# pylontec_LAN_interface.net
KiCad netlist of a schematic drawn in EAGLE
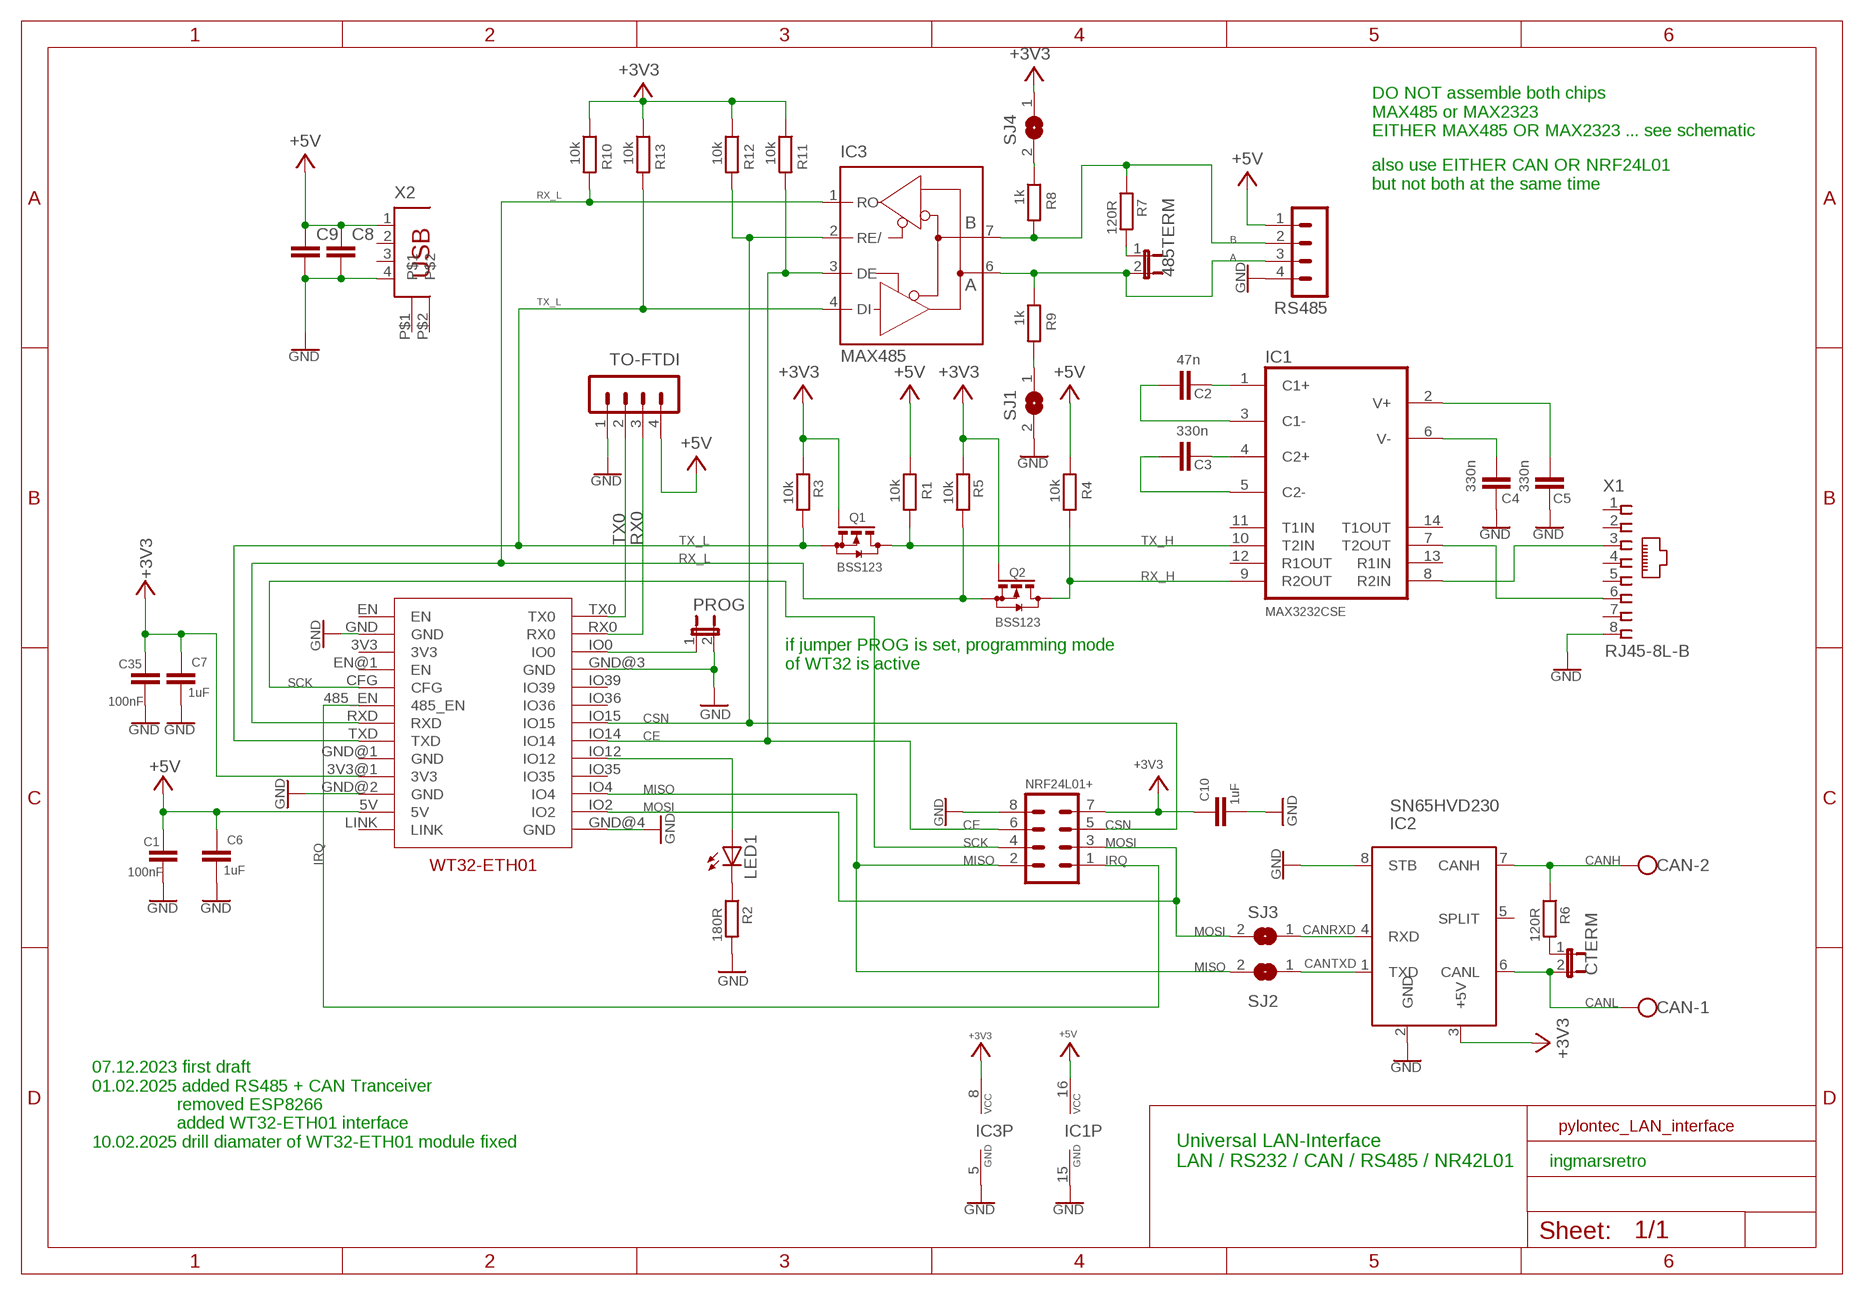
[diagram p0: schematic, sheet 1]

(export (version "E")
  (design (tool "Eeschema 10.0.6"))
  (components
    (comp (ref "485TERM")
      (value "JP1E")
      (footprint "eagle-import:JP1")
      (libsource (lib "eagle-import") (part "JP1E"))
    )
    (comp (ref "C1")
      (value "100nF")
      (footprint "eagle-import:C0805")
      (libsource (lib "eagle-import") (part "resistor_C-EUC0805"))
    )
    (comp (ref "C2")
      (value "47n")
      (footprint "eagle-import:C0805")
      (libsource (lib "eagle-import") (part "resistor_C-EUC0805"))
    )
    (comp (ref "C3")
      (value "330n")
      (footprint "eagle-import:C0805")
      (libsource (lib "eagle-import") (part "resistor_C-EUC0805"))
    )
    (comp (ref "C4")
      (value "330n")
      (footprint "eagle-import:C0805")
      (libsource (lib "eagle-import") (part "resistor_C-EUC0805"))
    )
    (comp (ref "C5")
      (value "330n")
      (footprint "eagle-import:C0805")
      (libsource (lib "eagle-import") (part "resistor_C-EUC0805"))
    )
    (comp (ref "C6")
      (value "1uF")
      (footprint "eagle-import:C1210")
      (libsource (lib "eagle-import") (part "C-EUC1210"))
    )
    (comp (ref "C7")
      (value "1uF")
      (footprint "eagle-import:C1210")
      (libsource (lib "eagle-import") (part "C-EUC1210"))
    )
    (comp (ref "C8")
      (value "C-EUC1210")
      (footprint "eagle-import:C1210")
      (libsource (lib "eagle-import") (part "C-EUC1210"))
    )
    (comp (ref "C9")
      (value "C-EUC1210")
      (footprint "eagle-import:C1210")
      (libsource (lib "eagle-import") (part "C-EUC1210"))
    )
    (comp (ref "C10")
      (value "1uF")
      (footprint "eagle-import:C1210")
      (libsource (lib "eagle-import") (part "C-EUC1210"))
    )
    (comp (ref "C35")
      (value "100nF")
      (footprint "eagle-import:C0805")
      (libsource (lib "eagle-import") (part "resistor_C-EUC0805"))
    )
    (comp (ref "CAN")
      (value "W237-102")
      (footprint "eagle-import:W237-102")
      (fields (field (name "MPN") "237-102"))
      (libsource (lib "eagle-import") (part "W237-102"))
    )
    (comp (ref "CTERM")
      (value "JP1E")
      (footprint "eagle-import:JP1")
      (libsource (lib "eagle-import") (part "JP1E"))
    )
    (comp (ref "IC1")
      (value "MAX3232CSE")
      (footprint "eagle-import:SO16")
      (libsource (lib "eagle-import") (part "MAX3232SEC"))
    )
    (comp (ref "IC2")
      (value "SN65HVD230")
      (footprint "eagle-import:SO8")
      (libsource (lib "eagle-import") (part "TJA1040"))
    )
    (comp (ref "IC3")
      (value "MAX485")
      (footprint "eagle-import:SO08")
      (fields (field (name "MF") "MAXIM") (field (name "MPN") "MAX481CSA"))
      (libsource (lib "eagle-import") (part "MAX481CSA"))
    )
    (comp (ref "LED1")
      (value "LED_LEDCHIPLED_0805")
      (footprint "eagle-import:LED_CHIPLED_0805")
      (libsource (lib "eagle-import") (part "LED_LEDCHIPLED_0805"))
    )
    (comp (ref "NRF24L01+")
      (value "MA04-2")
      (footprint "eagle-import:MA04-2")
      (libsource (lib "eagle-import") (part "MA04-2"))
    )
    (comp (ref "PROG")
      (value "JP1E")
      (footprint "eagle-import:JP1")
      (libsource (lib "eagle-import") (part "JP1E"))
    )
    (comp (ref "Q1")
      (value "BSS123")
      (footprint "eagle-import:SOT23")
      (libsource (lib "eagle-import") (part "BSS123"))
    )
    (comp (ref "Q2")
      (value "BSS123")
      (footprint "eagle-import:SOT23")
      (libsource (lib "eagle-import") (part "BSS123"))
    )
    (comp (ref "R1")
      (value "10k")
      (footprint "eagle-import:R0805")
      (libsource (lib "eagle-import") (part "R-EU_R0805"))
    )
    (comp (ref "R2")
      (value "180R")
      (footprint "eagle-import:R0805")
      (libsource (lib "eagle-import") (part "R-EU_R0805"))
    )
    (comp (ref "R3")
      (value "10k")
      (footprint "eagle-import:R0805")
      (libsource (lib "eagle-import") (part "R-EU_R0805"))
    )
    (comp (ref "R4")
      (value "10k")
      (footprint "eagle-import:R0805")
      (libsource (lib "eagle-import") (part "R-EU_R0805"))
    )
    (comp (ref "R5")
      (value "10k")
      (footprint "eagle-import:R0805")
      (libsource (lib "eagle-import") (part "R-EU_R0805"))
    )
    (comp (ref "R6")
      (value "120R")
      (footprint "eagle-import:R0805")
      (libsource (lib "eagle-import") (part "R-EU_R0805"))
    )
    (comp (ref "R7")
      (value "120R")
      (footprint "eagle-import:R0805")
      (libsource (lib "eagle-import") (part "R-EU_R0805"))
    )
    (comp (ref "R8")
      (value "1k")
      (footprint "eagle-import:R0805")
      (libsource (lib "eagle-import") (part "R-EU_R0805"))
    )
    (comp (ref "R9")
      (value "1k")
      (footprint "eagle-import:R0805")
      (libsource (lib "eagle-import") (part "R-EU_R0805"))
    )
    (comp (ref "R10")
      (value "10k")
      (footprint "eagle-import:R0805")
      (libsource (lib "eagle-import") (part "R-EU_R0805"))
    )
    (comp (ref "R11")
      (value "10k")
      (footprint "eagle-import:R0805")
      (libsource (lib "eagle-import") (part "R-EU_R0805"))
    )
    (comp (ref "R12")
      (value "10k")
      (footprint "eagle-import:R0805")
      (libsource (lib "eagle-import") (part "R-EU_R0805"))
    )
    (comp (ref "R13")
      (value "10k")
      (footprint "eagle-import:R0805")
      (libsource (lib "eagle-import") (part "R-EU_R0805"))
    )
    (comp (ref "RS485")
      (value "MA04-1")
      (footprint "eagle-import:MA04-1")
      (libsource (lib "eagle-import") (part "MA04-1"))
    )
    (comp (ref "SJ1") (value "SJ") (footprint "eagle-import:SJ") (libsource (lib "eagle-import") (part "SJ")))
    (comp (ref "SJ2") (value "SJ") (footprint "eagle-import:SJ") (libsource (lib "eagle-import") (part "SJ")))
    (comp (ref "SJ3") (value "SJ") (footprint "eagle-import:SJ") (libsource (lib "eagle-import") (part "SJ")))
    (comp (ref "SJ4") (value "SJ") (footprint "eagle-import:SJ") (libsource (lib "eagle-import") (part "SJ")))
    (comp (ref "TO-FTDI")
      (value "MA04-1")
      (footprint "eagle-import:MA04-1")
      (libsource (lib "eagle-import") (part "MA04-1"))
    )
    (comp (ref "U$2")
      (value "WT32-ETH01")
      (footprint "eagle-import:WT32-ETH01")
      (fields (field (name "MF") "wireless-tag"))
      (libsource (lib "eagle-import") (part "WT32-ETH01"))
    )
    (comp (ref "X1")
      (value "RJ45-8L-B")
      (footprint "eagle-import:RJ45-NO-SHIELD")
      (fields (field (name "MF") "TYCO ELECTRONICS"))
      (libsource (lib "eagle-import") (part "RJ45-8L-B"))
    )
    (comp (ref "X2")
      (value "SMARTPRJ_PN61729")
      (footprint "eagle-import:SMARTPRJ_PN61729")
      (libsource (lib "eagle-import") (part "SMARTPRJ_PN61729"))
    )
  )
  (nets
    (net (code "1") (name "+3V3") (class "Default")
      (node (ref "C10") (pin "1") (pinfunction "1_1") (pintype "passive"))
      (node (ref "C35") (pin "2") (pinfunction "2_2") (pintype "passive"))
      (node (ref "C7") (pin "1") (pinfunction "1_1") (pintype "passive"))
      (node (ref "IC2") (pin "3") (pinfunction "+5V_3") (pintype "bidirectional"))
      (node (ref "IC3") (pin "8") (pinfunction "VCC_8") (pintype "power_in"))
      (node (ref "NRF24L01+") (pin "7") (pinfunction "7_7") (pintype "passive"))
      (node (ref "Q1") (pin "1") (pinfunction "G_1") (pintype "passive"))
      (node (ref "Q2") (pin "1") (pinfunction "G_1") (pintype "passive"))
      (node (ref "R10") (pin "1") (pinfunction "1_1") (pintype "passive"))
      (node (ref "R11") (pin "1") (pinfunction "1_1") (pintype "passive"))
      (node (ref "R12") (pin "1") (pinfunction "1_1") (pintype "passive"))
      (node (ref "R13") (pin "1") (pinfunction "1_1") (pintype "passive"))
      (node (ref "R3") (pin "1") (pinfunction "1_1") (pintype "passive"))
      (node (ref "R5") (pin "1") (pinfunction "1_1") (pintype "passive"))
      (node (ref "SJ4") (pin "1") (pinfunction "1_1") (pintype "passive"))
      (node (ref "U$2") (pin "3V3@1") (pinfunction "3V3_3V3@1") (pintype "bidirectional"))
    )
    (net (code "2") (name "+5V") (class "Default")
      (node (ref "C1") (pin "2") (pinfunction "2_2") (pintype "passive"))
      (node (ref "C6") (pin "1") (pinfunction "1_1") (pintype "passive"))
      (node (ref "C8") (pin "1") (pinfunction "1_1") (pintype "passive"))
      (node (ref "C9") (pin "1") (pinfunction "1_1") (pintype "passive"))
      (node (ref "IC1") (pin "16") (pinfunction "VCC_16") (pintype "power_in"))
      (node (ref "R1") (pin "1") (pinfunction "1_1") (pintype "passive"))
      (node (ref "R4") (pin "1") (pinfunction "1_1") (pintype "passive"))
      (node (ref "RS485") (pin "1") (pinfunction "1_1") (pintype "passive"))
      (node (ref "TO-FTDI") (pin "4") (pinfunction "4_4") (pintype "passive"))
      (node (ref "U$2") (pin "5V") (pinfunction "5V_5V") (pintype "bidirectional"))
      (node (ref "X2") (pin "1") (pinfunction "1_1") (pintype "bidirectional"))
    )
    (net (code "3") (name "/A") (class "Default")
      (node (ref "485TERM") (pin "2") (pinfunction "2_2") (pintype "passive"))
      (node (ref "IC3") (pin "6") (pinfunction "A_6") (pintype "passive"))
      (node (ref "R9") (pin "1") (pinfunction "1_1") (pintype "passive"))
      (node (ref "RS485") (pin "3") (pinfunction "3_3") (pintype "passive"))
    )
    (net (code "4") (name "/B") (class "Default")
      (node (ref "IC3") (pin "7") (pinfunction "B_7") (pintype "passive"))
      (node (ref "R7") (pin "1") (pinfunction "1_1") (pintype "passive"))
      (node (ref "R8") (pin "2") (pinfunction "2_2") (pintype "passive"))
      (node (ref "RS485") (pin "2") (pinfunction "2_2") (pintype "passive"))
    )
    (net (code "5") (name "/CANH") (class "Default")
      (node (ref "CAN") (pin "2") (pinfunction "KL_2") (pintype "passive"))
      (node (ref "IC2") (pin "7") (pinfunction "CANH_7") (pintype "bidirectional"))
      (node (ref "R6") (pin "1") (pinfunction "1_1") (pintype "passive"))
    )
    (net (code "6") (name "/CANL") (class "Default")
      (node (ref "CAN") (pin "1") (pinfunction "KL_1") (pintype "passive"))
      (node (ref "CTERM") (pin "2") (pinfunction "2_2") (pintype "passive"))
      (node (ref "IC2") (pin "6") (pinfunction "CANL_6") (pintype "bidirectional"))
    )
    (net (code "7") (name "/CANRXD") (class "Default")
      (node (ref "IC2") (pin "4") (pinfunction "RXD_4") (pintype "bidirectional"))
      (node (ref "SJ3") (pin "1") (pinfunction "1_1") (pintype "passive"))
    )
    (net (code "8") (name "/CANTXD") (class "Default")
      (node (ref "IC2") (pin "1") (pinfunction "TXD_1") (pintype "bidirectional"))
      (node (ref "SJ2") (pin "1") (pinfunction "1_1") (pintype "passive"))
    )
    (net (code "9") (name "/CE") (class "Default")
      (node (ref "IC3") (pin "3") (pinfunction "DE_3") (pintype "input"))
      (node (ref "NRF24L01+") (pin "6") (pinfunction "6_6") (pintype "passive"))
      (node (ref "R11") (pin "2") (pinfunction "2_2") (pintype "passive"))
      (node (ref "U$2") (pin "IO14") (pinfunction "IO14_IO14") (pintype "bidirectional"))
    )
    (net (code "10") (name "/CSN") (class "Default")
      (node (ref "IC3") (pin "2") (pinfunction "RE/_2") (pintype "input"))
      (node (ref "NRF24L01+") (pin "5") (pinfunction "5_5") (pintype "passive"))
      (node (ref "R12") (pin "2") (pinfunction "2_2") (pintype "passive"))
      (node (ref "U$2") (pin "IO15") (pinfunction "IO15_IO15") (pintype "bidirectional"))
    )
    (net (code "11") (name "/IRQ") (class "Default")
      (node (ref "NRF24L01+") (pin "1") (pinfunction "1_1") (pintype "passive"))
      (node (ref "U$2") (pin "485_EN") (pinfunction "485_EN_485_EN") (pintype "bidirectional"))
    )
    (net (code "12") (name "/MISO") (class "Default")
      (node (ref "NRF24L01+") (pin "2") (pinfunction "2_2") (pintype "passive"))
      (node (ref "SJ2") (pin "2") (pinfunction "2_2") (pintype "passive"))
      (node (ref "U$2") (pin "IO4") (pinfunction "IO4_IO4") (pintype "bidirectional"))
    )
    (net (code "13") (name "/MOSI") (class "Default")
      (node (ref "NRF24L01+") (pin "3") (pinfunction "3_3") (pintype "passive"))
      (node (ref "SJ3") (pin "2") (pinfunction "2_2") (pintype "passive"))
      (node (ref "U$2") (pin "IO2") (pinfunction "IO2_IO2") (pintype "bidirectional"))
    )
    (net (code "14") (name "/RX0") (class "Default")
      (node (ref "TO-FTDI") (pin "3") (pinfunction "3_3") (pintype "passive"))
      (node (ref "U$2") (pin "RX0") (pinfunction "RX0_RX0") (pintype "bidirectional"))
    )
    (net (code "15") (name "/RX_H") (class "Default")
      (node (ref "IC1") (pin "9") (pinfunction "R2OUT_9") (pintype "output"))
      (node (ref "Q2") (pin "3") (pinfunction "D_3") (pintype "passive"))
      (node (ref "R4") (pin "2") (pinfunction "2_2") (pintype "passive"))
    )
    (net (code "16") (name "/RX_L") (class "Default")
      (node (ref "IC3") (pin "1") (pinfunction "RO_1") (pintype "output"))
      (node (ref "Q2") (pin "2") (pinfunction "S_2") (pintype "passive"))
      (node (ref "R10") (pin "2") (pinfunction "2_2") (pintype "passive"))
      (node (ref "R5") (pin "2") (pinfunction "2_2") (pintype "passive"))
      (node (ref "U$2") (pin "RXD") (pinfunction "RXD_RXD") (pintype "bidirectional"))
    )
    (net (code "17") (name "/SCK") (class "Default")
      (node (ref "NRF24L01+") (pin "4") (pinfunction "4_4") (pintype "passive"))
      (node (ref "U$2") (pin "CFG") (pinfunction "CFG_CFG") (pintype "bidirectional"))
    )
    (net (code "18") (name "/TX0") (class "Default")
      (node (ref "TO-FTDI") (pin "2") (pinfunction "2_2") (pintype "passive"))
      (node (ref "U$2") (pin "TX0") (pinfunction "TX0_TX0") (pintype "bidirectional"))
    )
    (net (code "19") (name "/TX_H") (class "Default")
      (node (ref "IC1") (pin "10") (pinfunction "T2IN_10") (pintype "input"))
      (node (ref "Q1") (pin "3") (pinfunction "D_3") (pintype "passive"))
      (node (ref "R1") (pin "2") (pinfunction "2_2") (pintype "passive"))
    )
    (net (code "20") (name "/TX_L") (class "Default")
      (node (ref "IC3") (pin "4") (pinfunction "DI_4") (pintype "input"))
      (node (ref "Q1") (pin "2") (pinfunction "S_2") (pintype "passive"))
      (node (ref "R13") (pin "2") (pinfunction "2_2") (pintype "passive"))
      (node (ref "R3") (pin "2") (pinfunction "2_2") (pintype "passive"))
      (node (ref "U$2") (pin "TXD") (pinfunction "TXD_TXD") (pintype "bidirectional"))
    )
    (net (code "21") (name "GND") (class "Default")
      (node (ref "C1") (pin "1") (pinfunction "1_1") (pintype "passive"))
      (node (ref "C10") (pin "2") (pinfunction "2_2") (pintype "passive"))
      (node (ref "C35") (pin "1") (pinfunction "1_1") (pintype "passive"))
      (node (ref "C4") (pin "2") (pinfunction "2_2") (pintype "passive"))
      (node (ref "C5") (pin "2") (pinfunction "2_2") (pintype "passive"))
      (node (ref "C6") (pin "2") (pinfunction "2_2") (pintype "passive"))
      (node (ref "C7") (pin "2") (pinfunction "2_2") (pintype "passive"))
      (node (ref "C8") (pin "2") (pinfunction "2_2") (pintype "passive"))
      (node (ref "C9") (pin "2") (pinfunction "2_2") (pintype "passive"))
      (node (ref "IC1") (pin "15") (pinfunction "GND_15") (pintype "power_in"))
      (node (ref "IC2") (pin "2") (pinfunction "GND_2") (pintype "bidirectional"))
      (node (ref "IC2") (pin "8") (pinfunction "STB_8") (pintype "bidirectional"))
      (node (ref "IC3") (pin "5") (pinfunction "GND_5") (pintype "power_in"))
      (node (ref "NRF24L01+") (pin "8") (pinfunction "8_8") (pintype "passive"))
      (node (ref "PROG") (pin "2") (pinfunction "2_2") (pintype "passive"))
      (node (ref "R2") (pin "2") (pinfunction "2_2") (pintype "passive"))
      (node (ref "RS485") (pin "4") (pinfunction "4_4") (pintype "passive"))
      (node (ref "SJ1") (pin "2") (pinfunction "2_2") (pintype "passive"))
      (node (ref "TO-FTDI") (pin "1") (pinfunction "1_1") (pintype "passive"))
      (node (ref "U$2") (pin "GND") (pinfunction "GND_GND") (pintype "bidirectional"))
      (node (ref "U$2") (pin "GND@2") (pinfunction "GND_GND@2") (pintype "bidirectional"))
      (node (ref "U$2") (pin "GND@3") (pinfunction "GND_GND@3") (pintype "bidirectional"))
      (node (ref "U$2") (pin "GND@4") (pinfunction "GND_GND@4") (pintype "bidirectional"))
      (node (ref "X1") (pin "8") (pinfunction "8_8") (pintype "passive"))
      (node (ref "X2") (pin "4") (pinfunction "4_4") (pintype "bidirectional"))
    )
    (net (code "22") (name "Net-(485TERM-Pad1)") (class "Default")
      (node (ref "485TERM") (pin "1") (pinfunction "1_1") (pintype "passive"))
      (node (ref "R7") (pin "2") (pinfunction "2_2") (pintype "passive"))
    )
    (net (code "23") (name "Net-(CTERM-Pad1)") (class "Default")
      (node (ref "CTERM") (pin "1") (pinfunction "1_1") (pintype "passive"))
      (node (ref "R6") (pin "2") (pinfunction "2_2") (pintype "passive"))
    )
    (net (code "24") (name "Net-(IC1A-C1+)") (class "Default")
      (node (ref "C2") (pin "1") (pinfunction "1_1") (pintype "passive"))
      (node (ref "IC1") (pin "1") (pinfunction "C1+_1") (pintype "bidirectional"))
    )
    (net (code "25") (name "Net-(IC1A-C1-)") (class "Default")
      (node (ref "C2") (pin "2") (pinfunction "2_2") (pintype "passive"))
      (node (ref "IC1") (pin "3") (pinfunction "C1-_3") (pintype "bidirectional"))
    )
    (net (code "26") (name "Net-(IC1A-C2+)") (class "Default")
      (node (ref "C3") (pin "1") (pinfunction "1_1") (pintype "passive"))
      (node (ref "IC1") (pin "4") (pinfunction "C2+_4") (pintype "bidirectional"))
    )
    (net (code "27") (name "Net-(IC1A-C2-)") (class "Default")
      (node (ref "C3") (pin "2") (pinfunction "2_2") (pintype "passive"))
      (node (ref "IC1") (pin "5") (pinfunction "C2-_5") (pintype "bidirectional"))
    )
    (net (code "28") (name "Net-(IC1A-R2IN)") (class "Default")
      (node (ref "IC1") (pin "8") (pinfunction "R2IN_8") (pintype "input"))
      (node (ref "X1") (pin "3") (pinfunction "3_3") (pintype "passive"))
    )
    (net (code "29") (name "Net-(IC1A-T2OUT)") (class "Default")
      (node (ref "IC1") (pin "7") (pinfunction "T2OUT_7") (pintype "output"))
      (node (ref "X1") (pin "6") (pinfunction "6_6") (pintype "passive"))
    )
    (net (code "30") (name "Net-(IC1A-V+)") (class "Default")
      (node (ref "C5") (pin "1") (pinfunction "1_1") (pintype "passive"))
      (node (ref "IC1") (pin "2") (pinfunction "V+_2") (pintype "bidirectional"))
    )
    (net (code "31") (name "Net-(IC1A-V-)") (class "Default")
      (node (ref "C4") (pin "1") (pinfunction "1_1") (pintype "passive"))
      (node (ref "IC1") (pin "6") (pinfunction "V-_6") (pintype "bidirectional"))
    )
    (net (code "32") (name "Net-(LED1-PadA)") (class "Default")
      (node (ref "LED1") (pin "A") (pinfunction "A_A") (pintype "passive"))
      (node (ref "U$2") (pin "IO12") (pinfunction "IO12_IO12") (pintype "bidirectional"))
    )
    (net (code "33") (name "Net-(LED1-PadC)") (class "Default")
      (node (ref "LED1") (pin "C") (pinfunction "C_C") (pintype "passive"))
      (node (ref "R2") (pin "1") (pinfunction "1_1") (pintype "passive"))
    )
    (net (code "34") (name "Net-(PROG-Pad1)") (class "Default")
      (node (ref "PROG") (pin "1") (pinfunction "1_1") (pintype "passive"))
      (node (ref "U$2") (pin "IO0") (pinfunction "IO0_IO0") (pintype "bidirectional"))
    )
    (net (code "35") (name "Net-(R8-Pad1)") (class "Default")
      (node (ref "R8") (pin "1") (pinfunction "1_1") (pintype "passive"))
      (node (ref "SJ4") (pin "2") (pinfunction "2_2") (pintype "passive"))
    )
    (net (code "36") (name "Net-(R9-Pad2)") (class "Default")
      (node (ref "R9") (pin "2") (pinfunction "2_2") (pintype "passive"))
      (node (ref "SJ1") (pin "1") (pinfunction "1_1") (pintype "passive"))
    )
    (net (code "37") (name "unconnected-(IC1A-R1IN-Pad13)") (class "Default")
      (node (ref "IC1") (pin "13") (pinfunction "R1IN_13") (pintype "input"))
    )
    (net (code "38") (name "unconnected-(IC1A-R1OUT-Pad12)") (class "Default")
      (node (ref "IC1") (pin "12") (pinfunction "R1OUT_12") (pintype "output"))
    )
    (net (code "39") (name "unconnected-(IC1A-T1IN-Pad11)") (class "Default")
      (node (ref "IC1") (pin "11") (pinfunction "T1IN_11") (pintype "input"))
    )
    (net (code "40") (name "unconnected-(IC1A-T1OUT-Pad14)") (class "Default")
      (node (ref "IC1") (pin "14") (pinfunction "T1OUT_14") (pintype "output"))
    )
    (net (code "41") (name "unconnected-(IC2-SPLIT-Pad5)") (class "Default")
      (node (ref "IC2") (pin "5") (pinfunction "SPLIT_5") (pintype "bidirectional"))
    )
    (net (code "42") (name "unconnected-(U$2-EN-PadEN@1)") (class "Default")
      (node (ref "U$2") (pin "EN@1") (pinfunction "EN_EN@1") (pintype "bidirectional"))
    )
    (net (code "43") (name "unconnected-(U$2-GND-PadGND@1)") (class "Default")
      (node (ref "U$2") (pin "GND@1") (pinfunction "GND_GND@1") (pintype "bidirectional"))
    )
    (net (code "44") (name "unconnected-(U$2-Pad3V3)") (class "Default")
      (node (ref "U$2") (pin "3V3") (pinfunction "3V3_3V3") (pintype "bidirectional"))
    )
    (net (code "45") (name "unconnected-(U$2-PadEN)") (class "Default")
      (node (ref "U$2") (pin "EN") (pinfunction "EN_EN") (pintype "bidirectional"))
    )
    (net (code "46") (name "unconnected-(U$2-PadIO35)") (class "Default")
      (node (ref "U$2") (pin "IO35") (pinfunction "IO35_IO35") (pintype "bidirectional"))
    )
    (net (code "47") (name "unconnected-(U$2-PadIO36)") (class "Default")
      (node (ref "U$2") (pin "IO36") (pinfunction "IO36_IO36") (pintype "bidirectional"))
    )
    (net (code "48") (name "unconnected-(U$2-PadIO39)") (class "Default")
      (node (ref "U$2") (pin "IO39") (pinfunction "IO39_IO39") (pintype "bidirectional"))
    )
    (net (code "49") (name "unconnected-(U$2-PadLINK)") (class "Default")
      (node (ref "U$2") (pin "LINK") (pinfunction "LINK_LINK") (pintype "bidirectional"))
    )
    (net (code "50") (name "unconnected-(X1-Pad1)") (class "Default")
      (node (ref "X1") (pin "1") (pinfunction "1_1") (pintype "passive"))
    )
    (net (code "51") (name "unconnected-(X1-Pad2)") (class "Default")
      (node (ref "X1") (pin "2") (pinfunction "2_2") (pintype "passive"))
    )
    (net (code "52") (name "unconnected-(X1-Pad4)") (class "Default")
      (node (ref "X1") (pin "4") (pinfunction "4_4") (pintype "passive"))
    )
    (net (code "53") (name "unconnected-(X1-Pad5)") (class "Default")
      (node (ref "X1") (pin "5") (pinfunction "5_5") (pintype "passive"))
    )
    (net (code "54") (name "unconnected-(X1-Pad7)") (class "Default")
      (node (ref "X1") (pin "7") (pinfunction "7_7") (pintype "passive"))
    )
    (net (code "55") (name "unconnected-(X2-Pad2)") (class "Default")
      (node (ref "X2") (pin "2") (pinfunction "2_2") (pintype "bidirectional"))
    )
    (net (code "56") (name "unconnected-(X2-Pad3)") (class "Default")
      (node (ref "X2") (pin "3") (pinfunction "3_3") (pintype "bidirectional"))
    )
    (net (code "57") (name "unconnected-(X2-PadP$1)") (class "Default")
      (node (ref "X2") (pin "P$1") (pinfunction "P$1_P$1") (pintype "bidirectional"))
    )
    (net (code "58") (name "unconnected-(X2-PadP$2)") (class "Default")
      (node (ref "X2") (pin "P$2") (pinfunction "P$2_P$2") (pintype "bidirectional"))
    )
  )
)
